# ETRX357.net
KiCad netlist of a schematic drawn in EAGLE
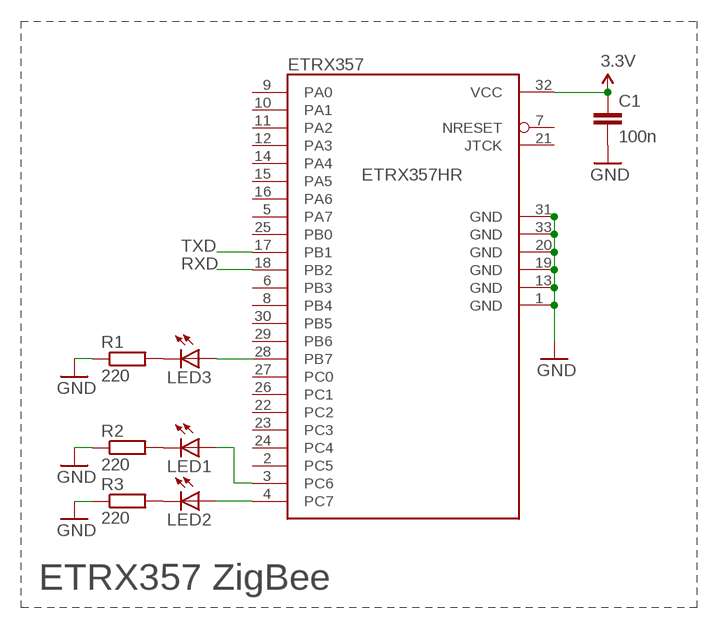
[diagram p0: schematic, sheet 1]

(export (version "E")
  (design (tool "Eeschema 10.0.6"))
  (components
    (comp (ref "C1")
      (value "100n")
      (footprint "eagle-import:C0805")
      (libsource (lib "eagle-import") (part "C-EUC0805"))
    )
    (comp (ref "ETRX357")
      (value "ETRX357HR")
      (footprint "eagle-import:ETRX3")
      (libsource (lib "eagle-import") (part "ETRX357HR"))
    )
    (comp (ref "LED1")
      (value "LED1206")
      (footprint "eagle-import:LED-1206")
      (libsource (lib "eagle-import") (part "LED1206"))
    )
    (comp (ref "LED2")
      (value "LED1206")
      (footprint "eagle-import:LED-1206")
      (libsource (lib "eagle-import") (part "LED1206"))
    )
    (comp (ref "LED3")
      (value "LED1206")
      (footprint "eagle-import:LED-1206")
      (libsource (lib "eagle-import") (part "LED1206"))
    )
    (comp (ref "R1")
      (value "220")
      (footprint "eagle-import:M0805")
      (libsource (lib "eagle-import") (part "R-EU_M0805"))
    )
    (comp (ref "R2")
      (value "220")
      (footprint "eagle-import:M0805")
      (libsource (lib "eagle-import") (part "R-EU_M0805"))
    )
    (comp (ref "R3")
      (value "220")
      (footprint "eagle-import:M0805")
      (libsource (lib "eagle-import") (part "R-EU_M0805"))
    )
  )
  (nets
    (net (code "1") (name "/RXD") (class "Default")
      (node (ref "ETRX357") (pin "18") (pinfunction "PB2_18") (pintype "bidirectional"))
    )
    (net (code "2") (name "/TXD") (class "Default")
      (node (ref "ETRX357") (pin "17") (pinfunction "PB1_17") (pintype "bidirectional"))
    )
    (net (code "3") (name "3.3V") (class "Default")
      (node (ref "C1") (pin "1") (pinfunction "1_1") (pintype "passive"))
      (node (ref "ETRX357") (pin "32") (pinfunction "VCC_32") (pintype "power_in"))
    )
    (net (code "4") (name "GND") (class "Default")
      (node (ref "C1") (pin "2") (pinfunction "2_2") (pintype "passive"))
      (node (ref "ETRX357") (pin "1") (pinfunction "GND_1") (pintype "power_in"))
      (node (ref "ETRX357") (pin "13") (pinfunction "GND_13") (pintype "power_in"))
      (node (ref "ETRX357") (pin "19") (pinfunction "GND_19") (pintype "power_in"))
      (node (ref "ETRX357") (pin "20") (pinfunction "GND_20") (pintype "power_in"))
      (node (ref "ETRX357") (pin "31") (pinfunction "GND_31") (pintype "power_in"))
      (node (ref "ETRX357") (pin "33") (pinfunction "GND_33") (pintype "power_in"))
      (node (ref "R1") (pin "1") (pinfunction "1_1") (pintype "passive"))
      (node (ref "R2") (pin "1") (pinfunction "1_1") (pintype "passive"))
      (node (ref "R3") (pin "1") (pinfunction "1_1") (pintype "passive"))
    )
    (net (code "5") (name "Net-(ETRX357-PB7)") (class "Default")
      (node (ref "ETRX357") (pin "28") (pinfunction "PB7_28") (pintype "bidirectional"))
      (node (ref "LED3") (pin "A") (pinfunction "A_A") (pintype "passive"))
    )
    (net (code "6") (name "Net-(ETRX357-PC6)") (class "Default")
      (node (ref "ETRX357") (pin "3") (pinfunction "PC6_3") (pintype "bidirectional"))
      (node (ref "LED1") (pin "A") (pinfunction "A_A") (pintype "passive"))
    )
    (net (code "7") (name "Net-(ETRX357-PC7)") (class "Default")
      (node (ref "ETRX357") (pin "4") (pinfunction "PC7_4") (pintype "bidirectional"))
      (node (ref "LED2") (pin "A") (pinfunction "A_A") (pintype "passive"))
    )
    (net (code "8") (name "Net-(LED1-PadC)") (class "Default")
      (node (ref "LED1") (pin "C") (pinfunction "C_C") (pintype "passive"))
      (node (ref "R2") (pin "2") (pinfunction "2_2") (pintype "passive"))
    )
    (net (code "9") (name "Net-(LED2-PadC)") (class "Default")
      (node (ref "LED2") (pin "C") (pinfunction "C_C") (pintype "passive"))
      (node (ref "R3") (pin "2") (pinfunction "2_2") (pintype "passive"))
    )
    (net (code "10") (name "Net-(LED3-PadC)") (class "Default")
      (node (ref "LED3") (pin "C") (pinfunction "C_C") (pintype "passive"))
      (node (ref "R1") (pin "2") (pinfunction "2_2") (pintype "passive"))
    )
    (net (code "11") (name "unconnected-(ETRX357-JTCK-Pad21)") (class "Default")
      (node (ref "ETRX357") (pin "21") (pinfunction "JTCK_21") (pintype "bidirectional"))
    )
    (net (code "12") (name "unconnected-(ETRX357-NRESET-Pad7)") (class "Default")
      (node (ref "ETRX357") (pin "7") (pinfunction "NRESET_7") (pintype "bidirectional"))
    )
    (net (code "13") (name "unconnected-(ETRX357-PA0-Pad9)") (class "Default")
      (node (ref "ETRX357") (pin "9") (pinfunction "PA0_9") (pintype "bidirectional"))
    )
    (net (code "14") (name "unconnected-(ETRX357-PA1-Pad10)") (class "Default")
      (node (ref "ETRX357") (pin "10") (pinfunction "PA1_10") (pintype "bidirectional"))
    )
    (net (code "15") (name "unconnected-(ETRX357-PA2-Pad11)") (class "Default")
      (node (ref "ETRX357") (pin "11") (pinfunction "PA2_11") (pintype "bidirectional"))
    )
    (net (code "16") (name "unconnected-(ETRX357-PA3-Pad12)") (class "Default")
      (node (ref "ETRX357") (pin "12") (pinfunction "PA3_12") (pintype "bidirectional"))
    )
    (net (code "17") (name "unconnected-(ETRX357-PA4-Pad14)") (class "Default")
      (node (ref "ETRX357") (pin "14") (pinfunction "PA4_14") (pintype "bidirectional"))
    )
    (net (code "18") (name "unconnected-(ETRX357-PA5-Pad15)") (class "Default")
      (node (ref "ETRX357") (pin "15") (pinfunction "PA5_15") (pintype "bidirectional"))
    )
    (net (code "19") (name "unconnected-(ETRX357-PA6-Pad16)") (class "Default")
      (node (ref "ETRX357") (pin "16") (pinfunction "PA6_16") (pintype "bidirectional"))
    )
    (net (code "20") (name "unconnected-(ETRX357-PA7-Pad5)") (class "Default")
      (node (ref "ETRX357") (pin "5") (pinfunction "PA7_5") (pintype "bidirectional"))
    )
    (net (code "21") (name "unconnected-(ETRX357-PB0-Pad25)") (class "Default")
      (node (ref "ETRX357") (pin "25") (pinfunction "PB0_25") (pintype "bidirectional"))
    )
    (net (code "22") (name "unconnected-(ETRX357-PB3-Pad6)") (class "Default")
      (node (ref "ETRX357") (pin "6") (pinfunction "PB3_6") (pintype "bidirectional"))
    )
    (net (code "23") (name "unconnected-(ETRX357-PB4-Pad8)") (class "Default")
      (node (ref "ETRX357") (pin "8") (pinfunction "PB4_8") (pintype "bidirectional"))
    )
    (net (code "24") (name "unconnected-(ETRX357-PB5-Pad30)") (class "Default")
      (node (ref "ETRX357") (pin "30") (pinfunction "PB5_30") (pintype "bidirectional"))
    )
    (net (code "25") (name "unconnected-(ETRX357-PB6-Pad29)") (class "Default")
      (node (ref "ETRX357") (pin "29") (pinfunction "PB6_29") (pintype "bidirectional"))
    )
    (net (code "26") (name "unconnected-(ETRX357-PC0-Pad27)") (class "Default")
      (node (ref "ETRX357") (pin "27") (pinfunction "PC0_27") (pintype "bidirectional"))
    )
    (net (code "27") (name "unconnected-(ETRX357-PC1-Pad26)") (class "Default")
      (node (ref "ETRX357") (pin "26") (pinfunction "PC1_26") (pintype "bidirectional"))
    )
    (net (code "28") (name "unconnected-(ETRX357-PC2-Pad22)") (class "Default")
      (node (ref "ETRX357") (pin "22") (pinfunction "PC2_22") (pintype "bidirectional"))
    )
    (net (code "29") (name "unconnected-(ETRX357-PC3-Pad23)") (class "Default")
      (node (ref "ETRX357") (pin "23") (pinfunction "PC3_23") (pintype "bidirectional"))
    )
    (net (code "30") (name "unconnected-(ETRX357-PC4-Pad24)") (class "Default")
      (node (ref "ETRX357") (pin "24") (pinfunction "PC4_24") (pintype "bidirectional"))
    )
    (net (code "31") (name "unconnected-(ETRX357-PC5-Pad2)") (class "Default")
      (node (ref "ETRX357") (pin "2") (pinfunction "PC5_2") (pintype "bidirectional"))
    )
  )
)
